# LB_BIT_1IN_3OUT-MEDIUM-v03_1_1x.net
KiCad netlist of a schematic drawn in EAGLE
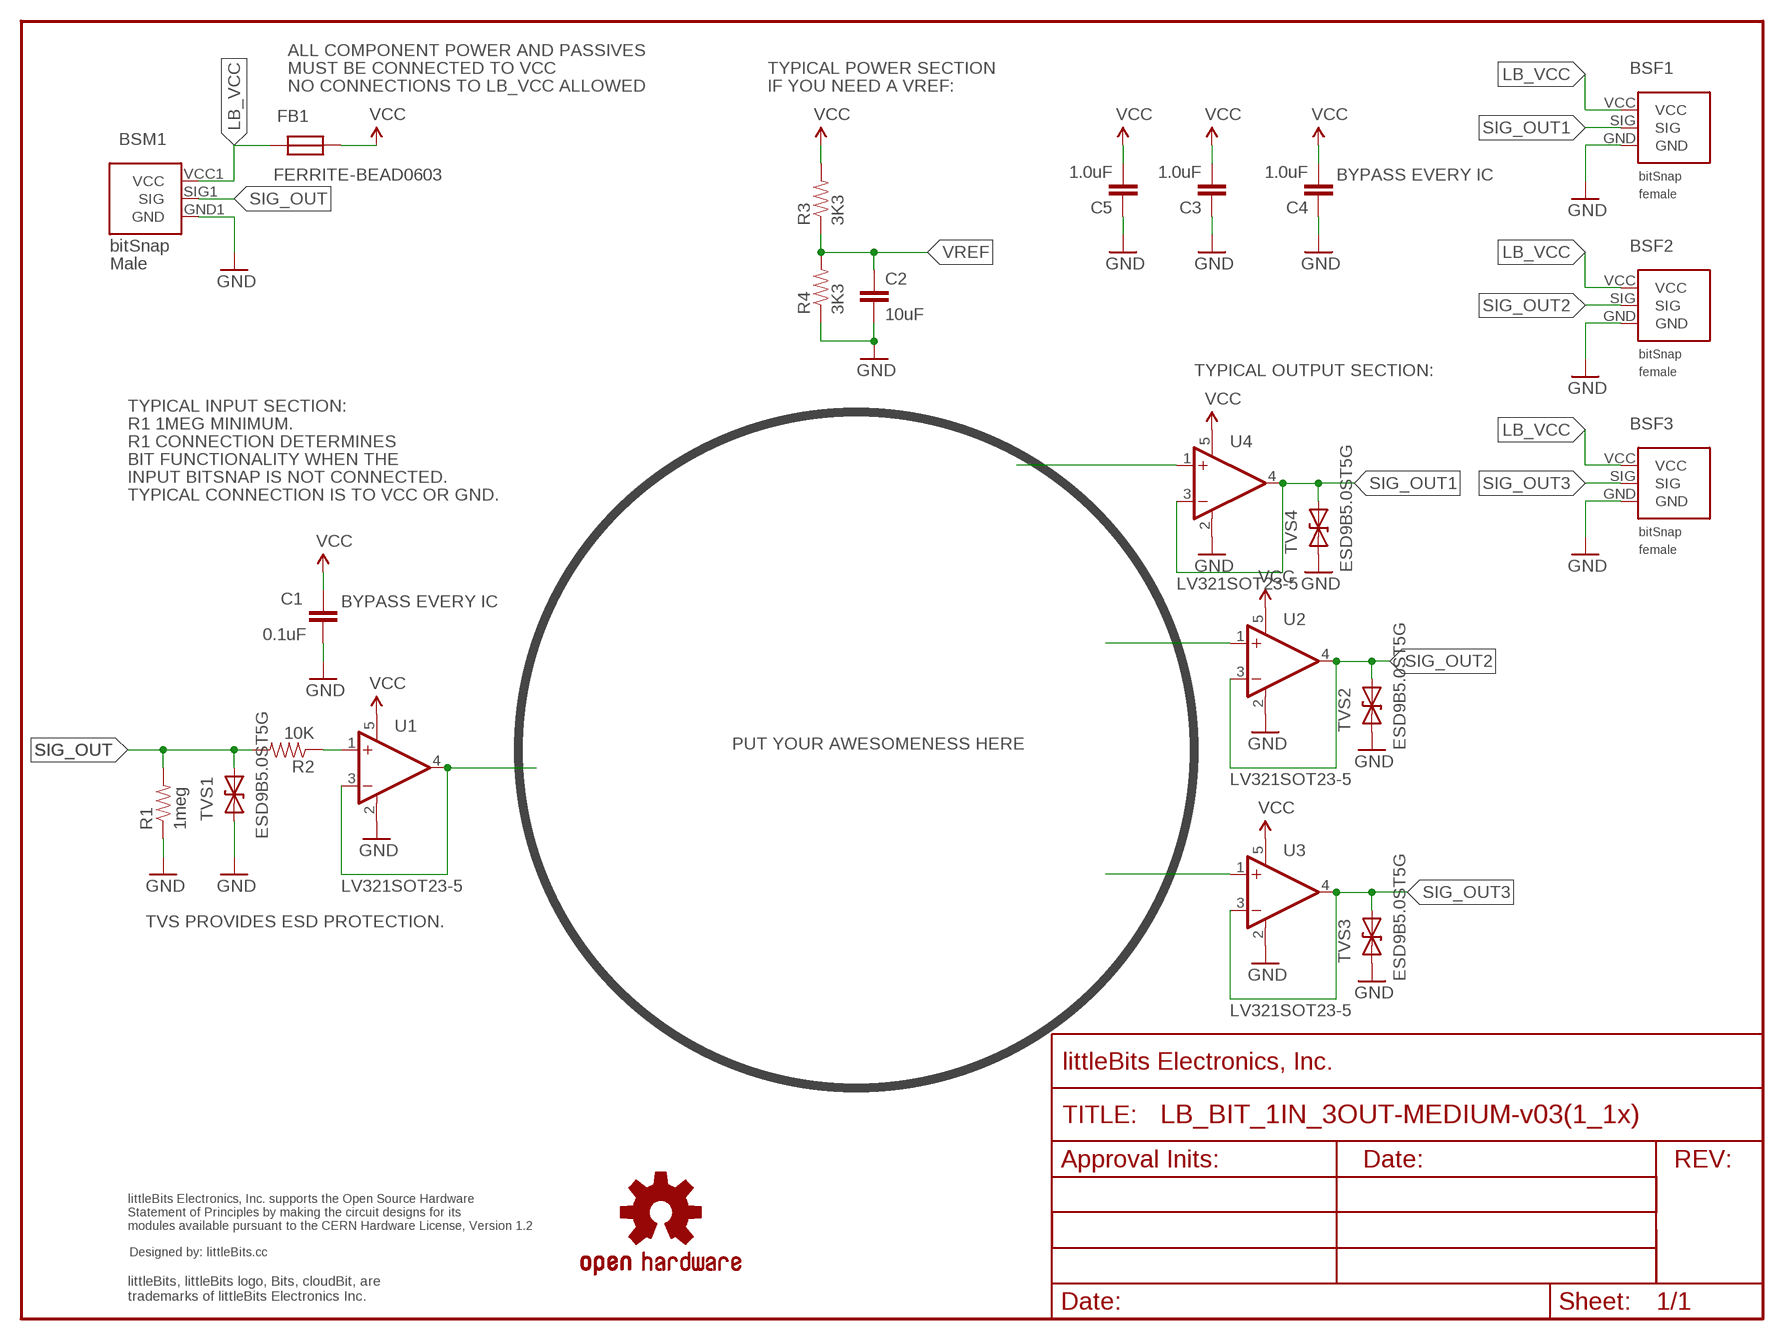
[diagram p0: schematic, sheet 1]

(export (version "E")
  (design (tool "Eeschema 10.0.6"))
  (components
    (comp (ref "BSF1")
      (value "BITSNAP_V03_FEMALE")
      (footprint "eagle-import:BITSNAP_V03_FEMALE")
      (libsource (lib "eagle-import") (part "BITSNAP_V03_FEMALE"))
    )
    (comp (ref "BSF2")
      (value "BITSNAP_V03_FEMALE")
      (footprint "eagle-import:BITSNAP_V03_FEMALE")
      (libsource (lib "eagle-import") (part "BITSNAP_V03_FEMALE"))
    )
    (comp (ref "BSF3")
      (value "BITSNAP_V03_FEMALE")
      (footprint "eagle-import:BITSNAP_V03_FEMALE")
      (libsource (lib "eagle-import") (part "BITSNAP_V03_FEMALE"))
    )
    (comp (ref "BSM1")
      (value "BITSNAP_V03_MALE")
      (footprint "eagle-import:BITSNAP_V03_MALE")
      (libsource (lib "eagle-import") (part "BITSNAP_V03_MALE"))
    )
    (comp (ref "C1")
      (value "0.1uF")
      (footprint "eagle-import:CAP-0603")
      (libsource (lib "eagle-import") (part "CAPCAP-0603"))
    )
    (comp (ref "C2")
      (value "10uF")
      (footprint "eagle-import:CAP-0603")
      (libsource (lib "eagle-import") (part "CAPCAP-0603"))
    )
    (comp (ref "C3")
      (value "1.0uF")
      (footprint "eagle-import:CAP-0603")
      (libsource (lib "eagle-import") (part "CAPCAP-0603"))
    )
    (comp (ref "C4")
      (value "1.0uF")
      (footprint "eagle-import:CAP-0603")
      (libsource (lib "eagle-import") (part "CAPCAP-0603"))
    )
    (comp (ref "C5")
      (value "1.0uF")
      (footprint "eagle-import:CAP-0603")
      (libsource (lib "eagle-import") (part "CAPCAP-0603"))
    )
    (comp (ref "FB1")
      (value "FERRITE-BEAD0603")
      (footprint "eagle-import:R0603")
      (libsource (lib "eagle-import") (part "FERRITE-BEAD0603"))
    )
    (comp (ref "FRAME1")
      (value "FRAME-LETTER")
      (footprint "eagle-import:FABDWG01-OHW")
      (libsource (lib "eagle-import") (part "FRAME-LETTER"))
    )
    (comp (ref "R1")
      (value "1meg")
      (footprint "eagle-import:RES-0603")
      (libsource (lib "eagle-import") (part "RESISTOR0603"))
    )
    (comp (ref "R2")
      (value "10K")
      (footprint "eagle-import:RES-0603")
      (libsource (lib "eagle-import") (part "RESISTOR0603"))
    )
    (comp (ref "R3")
      (value "3K3")
      (footprint "eagle-import:RES-0603")
      (libsource (lib "eagle-import") (part "RESISTOR0603"))
    )
    (comp (ref "R4")
      (value "3K3")
      (footprint "eagle-import:RES-0603")
      (libsource (lib "eagle-import") (part "RESISTOR0603"))
    )
    (comp (ref "TVS1")
      (value "ESD9B5.0ST5G")
      (footprint "eagle-import:SOD-923")
      (libsource (lib "eagle-import") (part "DIODE-TVSSOD-923"))
    )
    (comp (ref "TVS2")
      (value "ESD9B5.0ST5G")
      (footprint "eagle-import:SOD-923")
      (libsource (lib "eagle-import") (part "DIODE-TVSSOD-923"))
    )
    (comp (ref "TVS3")
      (value "ESD9B5.0ST5G")
      (footprint "eagle-import:SOD-923")
      (libsource (lib "eagle-import") (part "DIODE-TVSSOD-923"))
    )
    (comp (ref "TVS4")
      (value "ESD9B5.0ST5G")
      (footprint "eagle-import:SOD-923")
      (libsource (lib "eagle-import") (part "DIODE-TVSSOD-923"))
    )
    (comp (ref "U$2")
      (value "OSHWCREDIT")
      (footprint "eagle-import:OSHWCREDIT")
      (libsource (lib "eagle-import") (part "OSHWCREDIT"))
    )
    (comp (ref "U$3")
      (value "OSHW-LOGOL")
      (footprint "eagle-import:OSHW-LOGO-L")
      (libsource (lib "eagle-import") (part "OSHW-LOGOL"))
    )
    (comp (ref "U1")
      (value "LV321SOT23-5")
      (footprint "eagle-import:SOT23-5")
      (libsource (lib "eagle-import") (part "LV321SOT23-5"))
    )
    (comp (ref "U2")
      (value "LV321SOT23-5")
      (footprint "eagle-import:SOT23-5")
      (libsource (lib "eagle-import") (part "LV321SOT23-5"))
    )
    (comp (ref "U3")
      (value "LV321SOT23-5")
      (footprint "eagle-import:SOT23-5")
      (libsource (lib "eagle-import") (part "LV321SOT23-5"))
    )
    (comp (ref "U4")
      (value "LV321SOT23-5")
      (footprint "eagle-import:SOT23-5")
      (libsource (lib "eagle-import") (part "LV321SOT23-5"))
    )
  )
  (nets
    (net (code "1") (name "GND") (class "Default")
      (node (ref "BSF1") (pin "GND") (pinfunction "GND_GND") (pintype "bidirectional"))
      (node (ref "BSF2") (pin "GND") (pinfunction "GND_GND") (pintype "bidirectional"))
      (node (ref "BSF3") (pin "GND") (pinfunction "GND_GND") (pintype "bidirectional"))
      (node (ref "BSM1") (pin "GND1") (pinfunction "GND_GND1") (pintype "bidirectional"))
      (node (ref "C1") (pin "2") (pinfunction "2_2") (pintype "passive"))
      (node (ref "C2") (pin "2") (pinfunction "2_2") (pintype "passive"))
      (node (ref "C3") (pin "1") (pinfunction "1_1") (pintype "passive"))
      (node (ref "C4") (pin "1") (pinfunction "1_1") (pintype "passive"))
      (node (ref "C5") (pin "1") (pinfunction "1_1") (pintype "passive"))
      (node (ref "R1") (pin "1") (pinfunction "1_1") (pintype "passive"))
      (node (ref "R4") (pin "1") (pinfunction "1_1") (pintype "passive"))
      (node (ref "TVS1") (pin "1") (pinfunction "A_1") (pintype "passive"))
      (node (ref "TVS2") (pin "1") (pinfunction "A_1") (pintype "passive"))
      (node (ref "TVS3") (pin "1") (pinfunction "A_1") (pintype "passive"))
      (node (ref "TVS4") (pin "1") (pinfunction "A_1") (pintype "passive"))
      (node (ref "U1") (pin "2") (pinfunction "V-_2") (pintype "power_in"))
      (node (ref "U2") (pin "2") (pinfunction "V-_2") (pintype "power_in"))
      (node (ref "U3") (pin "2") (pinfunction "V-_2") (pintype "power_in"))
      (node (ref "U4") (pin "2") (pinfunction "V-_2") (pintype "power_in"))
    )
    (net (code "2") (name "LB_VCC") (class "Default")
      (node (ref "BSF1") (pin "VCC") (pinfunction "VCC_VCC") (pintype "bidirectional"))
      (node (ref "BSF2") (pin "VCC") (pinfunction "VCC_VCC") (pintype "bidirectional"))
      (node (ref "BSF3") (pin "VCC") (pinfunction "VCC_VCC") (pintype "bidirectional"))
      (node (ref "BSM1") (pin "VCC1") (pinfunction "VCC_VCC1") (pintype "bidirectional"))
      (node (ref "FB1") (pin "2") (pinfunction "P$2_2") (pintype "bidirectional"))
    )
    (net (code "3") (name "Net-(U1-+IN)") (class "Default")
      (node (ref "R2") (pin "1") (pinfunction "1_1") (pintype "passive"))
      (node (ref "U1") (pin "1") (pinfunction "+IN_1") (pintype "input"))
    )
    (net (code "4") (name "Net-(U1--IN)") (class "Default")
      (node (ref "U1") (pin "3") (pinfunction "-IN_3") (pintype "input"))
      (node (ref "U1") (pin "4") (pinfunction "OUT_4") (pintype "output"))
    )
    (net (code "5") (name "SIG_OUT") (class "Default")
      (node (ref "BSM1") (pin "SIG1") (pinfunction "SIG_SIG1") (pintype "bidirectional"))
      (node (ref "R1") (pin "2") (pinfunction "2_2") (pintype "passive"))
      (node (ref "R2") (pin "2") (pinfunction "2_2") (pintype "passive"))
      (node (ref "TVS1") (pin "2") (pinfunction "C_2") (pintype "passive"))
    )
    (net (code "6") (name "SIG_OUT1") (class "Default")
      (node (ref "BSF1") (pin "SIG") (pinfunction "SIG_SIG") (pintype "bidirectional"))
      (node (ref "TVS4") (pin "2") (pinfunction "C_2") (pintype "passive"))
      (node (ref "U4") (pin "3") (pinfunction "-IN_3") (pintype "input"))
      (node (ref "U4") (pin "4") (pinfunction "OUT_4") (pintype "output"))
    )
    (net (code "7") (name "SIG_OUT2") (class "Default")
      (node (ref "BSF2") (pin "SIG") (pinfunction "SIG_SIG") (pintype "bidirectional"))
      (node (ref "TVS2") (pin "2") (pinfunction "C_2") (pintype "passive"))
      (node (ref "U2") (pin "3") (pinfunction "-IN_3") (pintype "input"))
      (node (ref "U2") (pin "4") (pinfunction "OUT_4") (pintype "output"))
    )
    (net (code "8") (name "SIG_OUT3") (class "Default")
      (node (ref "BSF3") (pin "SIG") (pinfunction "SIG_SIG") (pintype "bidirectional"))
      (node (ref "TVS3") (pin "2") (pinfunction "C_2") (pintype "passive"))
      (node (ref "U3") (pin "3") (pinfunction "-IN_3") (pintype "input"))
      (node (ref "U3") (pin "4") (pinfunction "OUT_4") (pintype "output"))
    )
    (net (code "9") (name "VCC") (class "Default")
      (node (ref "C1") (pin "1") (pinfunction "1_1") (pintype "passive"))
      (node (ref "C3") (pin "2") (pinfunction "2_2") (pintype "passive"))
      (node (ref "C4") (pin "2") (pinfunction "2_2") (pintype "passive"))
      (node (ref "C5") (pin "2") (pinfunction "2_2") (pintype "passive"))
      (node (ref "FB1") (pin "1") (pinfunction "P$1_1") (pintype "bidirectional"))
      (node (ref "R3") (pin "2") (pinfunction "2_2") (pintype "passive"))
      (node (ref "U1") (pin "5") (pinfunction "V+_5") (pintype "power_in"))
      (node (ref "U2") (pin "5") (pinfunction "V+_5") (pintype "power_in"))
      (node (ref "U3") (pin "5") (pinfunction "V+_5") (pintype "power_in"))
      (node (ref "U4") (pin "5") (pinfunction "V+_5") (pintype "power_in"))
    )
    (net (code "10") (name "VREF") (class "Default")
      (node (ref "C2") (pin "1") (pinfunction "1_1") (pintype "passive"))
      (node (ref "R3") (pin "1") (pinfunction "1_1") (pintype "passive"))
      (node (ref "R4") (pin "2") (pinfunction "2_2") (pintype "passive"))
    )
    (net (code "11") (name "unconnected-(U2-+IN-Pad1)") (class "Default")
      (node (ref "U2") (pin "1") (pinfunction "+IN_1") (pintype "input"))
    )
    (net (code "12") (name "unconnected-(U3-+IN-Pad1)") (class "Default")
      (node (ref "U3") (pin "1") (pinfunction "+IN_1") (pintype "input"))
    )
    (net (code "13") (name "unconnected-(U4-+IN-Pad1)") (class "Default")
      (node (ref "U4") (pin "1") (pinfunction "+IN_1") (pintype "input"))
    )
  )
)
